# HA_Diagram.net
KiCad netlist of a schematic drawn in Altium Designer
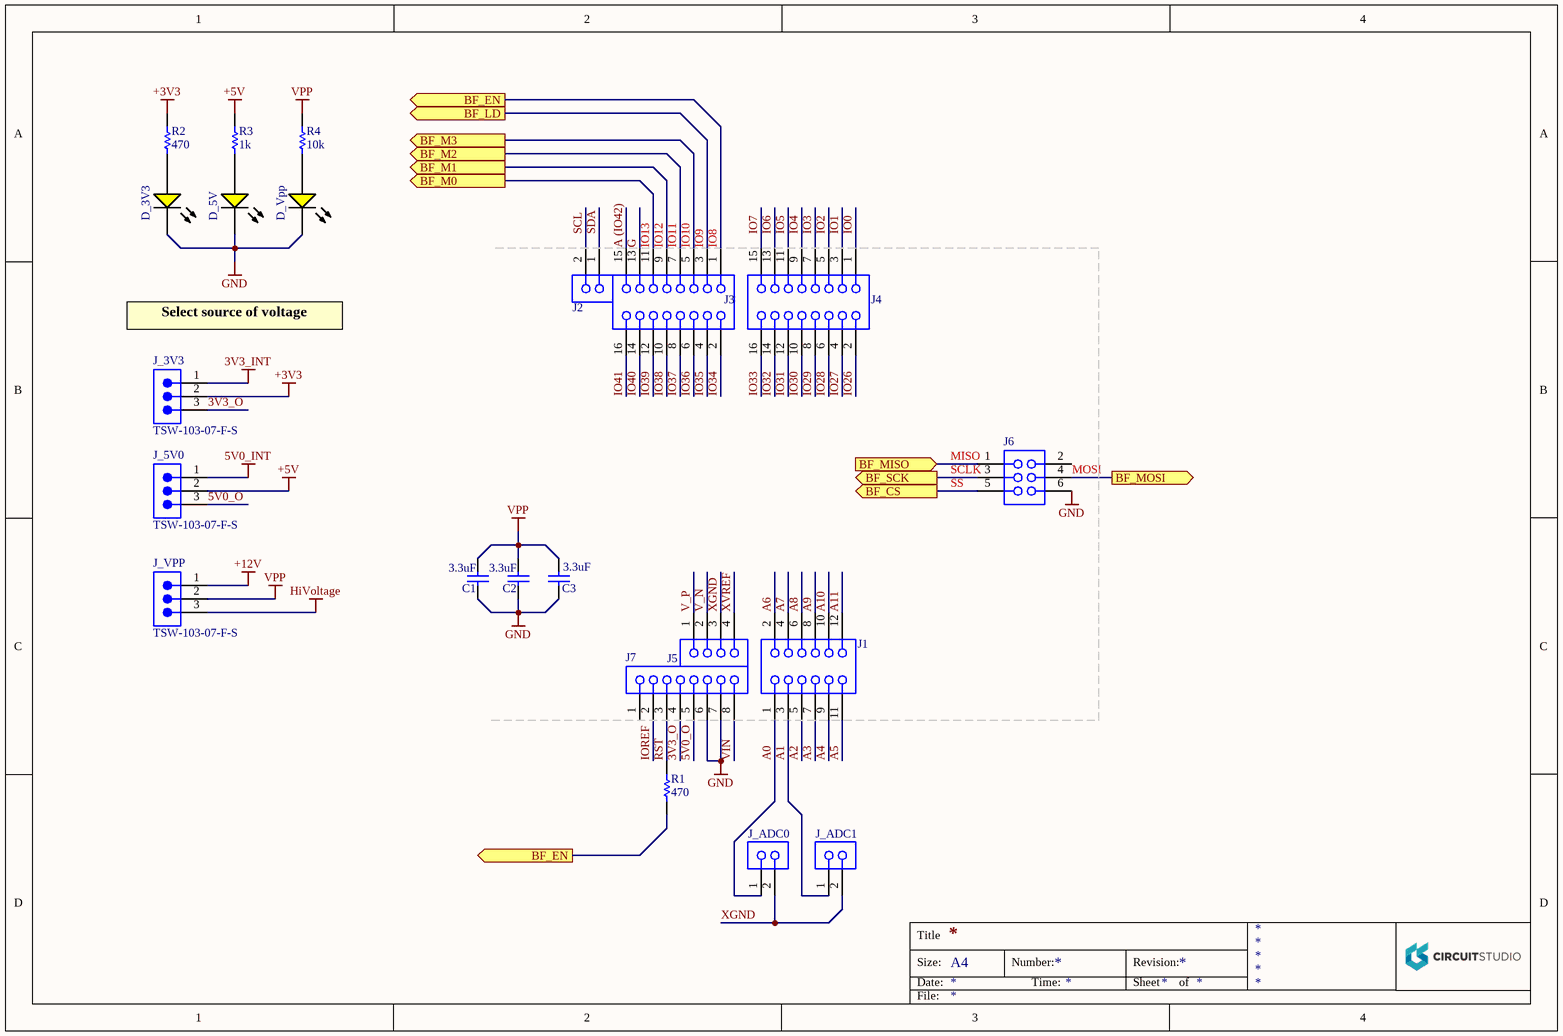
[diagram p0: HA_Diagram.SchDoc]

(export (version "E")
  (design (tool "Eeschema 10.0.6"))
  (components
    (comp (ref "C1")
      (value "3.3uF")
      (footprint "CAPC1206(3216)190_N")
      (description "CAP 3.3uF 100V ±20% 1206 (3216 Metric) Thickness 1.9mm SMD")
      (fields (field (name "TOLERANCE") "Â±20%") (field (name "Comment") "3.3uF 100V"))
      (libsource (lib "Altium Content Vault") (part "CMP-1037-04411-1"))
    )
    (comp (ref "C2")
      (value "3.3uF")
      (footprint "CAPC1206(3216)190_N")
      (description "CAP 3.3uF 100V ±20% 1206 (3216 Metric) Thickness 1.9mm SMD")
      (fields (field (name "TOLERANCE") "Â±20%") (field (name "Comment") "3.3uF 100V"))
      (libsource (lib "Altium Content Vault") (part "CMP-1037-04411-1"))
    )
    (comp (ref "C3")
      (value "3.3uF")
      (footprint "CAPC1206(3216)190_N")
      (description "CAP 3.3uF 100V ±20% 1206 (3216 Metric) Thickness 1.9mm SMD")
      (fields (field (name "TOLERANCE") "Â±20%") (field (name "Comment") "3.3uF 100V"))
      (libsource (lib "Altium Content Vault") (part "CMP-1037-04411-1"))
    )
    (comp (ref "D_3V3")
      (value "LED 0603")
      (footprint "LTST-C190KSKT_V")
      (fields (field (name "TOLERANCE") "1%"))
      (libsource (lib "Altium Content Vault") (part "CMP-1674-00009-1"))
    )
    (comp (ref "D_5V")
      (value "LED 0603")
      (footprint "LTST-C190KSKT_V")
      (fields (field (name "TOLERANCE") "1%"))
      (libsource (lib "Altium Content Vault") (part "CMP-1674-00009-1"))
    )
    (comp (ref "D_Vpp")
      (value "LED 0603")
      (footprint "LTST-C190KSKT_V")
      (fields (field (name "TOLERANCE") "1%"))
      (libsource (lib "Altium Content Vault") (part "CMP-1674-00009-1"))
    )
    (comp (ref "J1")
      (value "SSW-106-01-F-D")
      (footprint "SMTC-SSW-106-01-X-D")
      (description "SQ Post Socket, Through-hole, Vertical, -55 to 125 degC, 2.54mm Pitch, 12-Pin, Female, RoHS")
      (fields (field (name "MANUFACTURER") "Samtec"))
      (libsource (lib "Altium Content Vault") (part "CMP-1023-00357-1"))
    )
    (comp (ref "J2")
      (value "PHF-102-03-L-S")
      (footprint "SMTC-PHF-102-03-X-S")
      (description "Press Fit Socket, Through-hole, Vertical, -55 to 125 degC, 2.54 mm Pitch, 2-Pin, Female, RoHS")
      (fields (field (name "MANUFACTURER") "Samtec"))
      (libsource (lib "") (part "CMP-1023-00105-1_1"))
    )
    (comp (ref "J3")
      (value "ESW-108-12-G-D")
      (footprint "SMTC-ESW-108-12-X-D")
      (description "Elevated Socket, Through-hole, Vertical, -55 to 125 degC, 2.54 mm Pitch, 16-Pin, Female, RoHS")
      (fields (field (name "MANUFACTURER") "Samtec"))
      (libsource (lib "Altium Content Vault") (part "CMP-1023-00046-1"))
    )
    (comp (ref "J4")
      (value "ESW-108-12-G-D")
      (footprint "SMTC-ESW-108-12-X-D")
      (description "Elevated Socket, Through-hole, Vertical, -55 to 125 degC, 2.54 mm Pitch, 16-Pin, Female, RoHS")
      (fields (field (name "MANUFACTURER") "Samtec"))
      (libsource (lib "Altium Content Vault") (part "CMP-1023-00046-1"))
    )
    (comp (ref "J5")
      (value "SLW-104-01-F-S")
      (footprint "SMTC-SLW-104-01-X-S")
      (fields (field (name "MANUFACTURER") "Samtec"))
      (libsource (lib "Altium Content Vault") (part "CMP-1023-00132-1"))
    )
    (comp (ref "J6")
      (value "SSW-103-01-F-D")
      (footprint "SMTC-SSW-103-01-X-D")
      (description "SQ Post Socket, Through-hole, Vertical, -55 to 125 degC, 2.54 mm Pitch, 6-Pin, Female, RoHS")
      (fields (field (name "MANUFACTURER") "Samtec"))
      (libsource (lib "Altium Content Vault") (part "CMP-1023-00329-1"))
    )
    (comp (ref "J7")
      (value "SSQ-108-01-F-S")
      (footprint "SMTC-SSQ-108-01-X-S")
      (description "SQ Post Socket, Through-hole, Vertical, -55 to 125 degC, 2.54 mm Pitch, 8-Pin, Female, RoHS")
      (fields (field (name "MANUFACTURER") "Samtec"))
      (libsource (lib "Altium Content Vault") (part "CMP-1023-00294-1"))
    )
    (comp (ref "J_3V3")
      (value "TSW-103-07-F-S")
      (footprint "SMTC-TSW-103-07-X-S")
      (description "0.025\" SQ Post Header, Through-hole, Vertical, -55 to 125 degC, 2.54 mm Pitch, 3-Pin, Male, RoHS")
      (fields (field (name "MANUFACTURER") "Samtec"))
      (libsource (lib "Altium Content Vault") (part "CMP-1024-00331-1"))
    )
    (comp (ref "J_5V0")
      (value "TSW-103-07-F-S")
      (footprint "SMTC-TSW-103-07-X-S")
      (description "0.025\" SQ Post Header, Through-hole, Vertical, -55 to 125 degC, 2.54 mm Pitch, 3-Pin, Male, RoHS")
      (fields (field (name "MANUFACTURER") "Samtec"))
      (libsource (lib "Altium Content Vault") (part "CMP-1024-00331-1"))
    )
    (comp (ref "J_ADC0")
      (value "PHF-102-03-L-S")
      (footprint "SMTC-PHF-102-03-X-S")
      (description "Press Fit Socket, Through-hole, Vertical, -55 to 125 degC, 2.54 mm Pitch, 2-Pin, Female, RoHS")
      (fields (field (name "MANUFACTURER") "Samtec"))
      (libsource (lib "Altium Content Vault") (part "CMP-1023-00105-1"))
    )
    (comp (ref "J_ADC1")
      (value "PHF-102-03-L-S")
      (footprint "SMTC-PHF-102-03-X-S")
      (description "Press Fit Socket, Through-hole, Vertical, -55 to 125 degC, 2.54 mm Pitch, 2-Pin, Female, RoHS")
      (fields (field (name "MANUFACTURER") "Samtec"))
      (libsource (lib "Altium Content Vault") (part "CMP-1023-00105-1"))
    )
    (comp (ref "J_VPP")
      (value "TSW-103-07-F-S")
      (footprint "SMTC-TSW-103-07-X-S")
      (description "0.025\" SQ Post Header, Through-hole, Vertical, -55 to 125 degC, 2.54 mm Pitch, 3-Pin, Male, RoHS")
      (fields (field (name "MANUFACTURER") "Samtec"))
      (libsource (lib "Altium Content Vault") (part "CMP-1024-00331-1"))
    )
    (comp (ref "R1")
      (value "470")
      (footprint "RESC0603(1608)_N")
      (description "200 1% 0603 SMD")
      (fields (field (name "TOLERANCE") "1 %"))
      (libsource (lib "Altium Content Vault") (part "CMP-1012-00122-1"))
    )
    (comp (ref "R2")
      (value "470")
      (footprint "RESC0603(1608)_N")
      (description "200 1% 0603 SMD")
      (fields (field (name "TOLERANCE") "1 %"))
      (libsource (lib "Altium Content Vault") (part "CMP-1012-00122-1"))
    )
    (comp (ref "R3")
      (value "1k")
      (footprint "RESC0603(1608)_N")
      (description "200 1% 0603 SMD")
      (fields (field (name "TOLERANCE") "1 %"))
      (libsource (lib "Altium Content Vault") (part "CMP-1012-00122-1"))
    )
    (comp (ref "R4")
      (value "10k")
      (footprint "RESC0603(1608)_N")
      (description "200 1% 0603 SMD")
      (fields (field (name "TOLERANCE") "1 %"))
      (libsource (lib "Altium Content Vault") (part "CMP-1012-00122-1"))
    )
  )
  (nets
    (net (code "1") (name "+3V3") (class "Default")
      (node (ref "J_3V3") (pin "2") (pinfunction "2_2") (pintype "passive"))
      (node (ref "R2") (pin "1") (pinfunction "1_1") (pintype "passive"))
    )
    (net (code "2") (name "+5V") (class "Default")
      (node (ref "J_5V0") (pin "2") (pinfunction "2_2") (pintype "passive"))
      (node (ref "R3") (pin "1") (pinfunction "1_1") (pintype "passive"))
    )
    (net (code "3") (name "+12V") (class "Default")
      (node (ref "J_VPP") (pin "1") (pinfunction "1_1") (pintype "passive"))
    )
    (net (code "4") (name "/3V3_O") (class "Default")
      (node (ref "J7") (pin "4") (pinfunction "4_4") (pintype "passive"))
      (node (ref "J_3V3") (pin "3") (pinfunction "3_3") (pintype "passive"))
    )
    (net (code "5") (name "/5V0_O") (class "Default")
      (node (ref "J7") (pin "5") (pinfunction "5_5") (pintype "passive"))
      (node (ref "J_5V0") (pin "3") (pinfunction "3_3") (pintype "passive"))
    )
    (net (code "6") (name "/A (IO42)") (class "Default")
      (node (ref "J3") (pin "15") (pinfunction "15_15") (pintype "passive"))
    )
    (net (code "7") (name "/A0") (class "Default")
      (node (ref "J1") (pin "1") (pinfunction "1_1") (pintype "passive"))
      (node (ref "J_ADC0") (pin "1") (pinfunction "1_1") (pintype "passive"))
    )
    (net (code "8") (name "/A1") (class "Default")
      (node (ref "J1") (pin "3") (pinfunction "3_3") (pintype "passive"))
      (node (ref "J_ADC1") (pin "1") (pinfunction "1_1") (pintype "passive"))
    )
    (net (code "9") (name "/A2") (class "Default")
      (node (ref "J1") (pin "5") (pinfunction "5_5") (pintype "passive"))
    )
    (net (code "10") (name "/A3") (class "Default")
      (node (ref "J1") (pin "7") (pinfunction "7_7") (pintype "passive"))
    )
    (net (code "11") (name "/A4") (class "Default")
      (node (ref "J1") (pin "9") (pinfunction "9_9") (pintype "passive"))
    )
    (net (code "12") (name "/A5") (class "Default")
      (node (ref "J1") (pin "11") (pinfunction "11_11") (pintype "passive"))
    )
    (net (code "13") (name "/A6") (class "Default")
      (node (ref "J1") (pin "2") (pinfunction "2_2") (pintype "passive"))
    )
    (net (code "14") (name "/A7") (class "Default")
      (node (ref "J1") (pin "4") (pinfunction "4_4") (pintype "passive"))
    )
    (net (code "15") (name "/A8") (class "Default")
      (node (ref "J1") (pin "6") (pinfunction "6_6") (pintype "passive"))
    )
    (net (code "16") (name "/A9") (class "Default")
      (node (ref "J1") (pin "8") (pinfunction "8_8") (pintype "passive"))
    )
    (net (code "17") (name "/A10") (class "Default")
      (node (ref "J1") (pin "10") (pinfunction "10_10") (pintype "passive"))
    )
    (net (code "18") (name "/A11") (class "Default")
      (node (ref "J1") (pin "12") (pinfunction "12_12") (pintype "passive"))
    )
    (net (code "19") (name "/BF_CS") (class "Default")
      (node (ref "J6") (pin "5") (pinfunction "5_5") (pintype "passive"))
    )
    (net (code "20") (name "/BF_EN") (class "Default")
      (node (ref "J3") (pin "1") (pinfunction "1_1") (pintype "passive"))
      (node (ref "R1") (pin "2") (pinfunction "2_2") (pintype "passive"))
    )
    (net (code "21") (name "/BF_LD") (class "Default")
      (node (ref "J3") (pin "3") (pinfunction "3_3") (pintype "passive"))
    )
    (net (code "22") (name "/BF_M0") (class "Default")
      (node (ref "J3") (pin "11") (pinfunction "11_11") (pintype "passive"))
    )
    (net (code "23") (name "/BF_M1") (class "Default")
      (node (ref "J3") (pin "9") (pinfunction "9_9") (pintype "passive"))
    )
    (net (code "24") (name "/BF_M2") (class "Default")
      (node (ref "J3") (pin "7") (pinfunction "7_7") (pintype "passive"))
    )
    (net (code "25") (name "/BF_M3") (class "Default")
      (node (ref "J3") (pin "5") (pinfunction "5_5") (pintype "passive"))
    )
    (net (code "26") (name "/BF_MISO") (class "Default")
      (node (ref "J6") (pin "1") (pinfunction "1_1") (pintype "passive"))
    )
    (net (code "27") (name "/BF_MOSI") (class "Default")
      (node (ref "J6") (pin "4") (pinfunction "4_4") (pintype "passive"))
    )
    (net (code "28") (name "/BF_SCK") (class "Default")
      (node (ref "J6") (pin "3") (pinfunction "3_3") (pintype "passive"))
    )
    (net (code "29") (name "/G") (class "Default")
      (node (ref "J3") (pin "13") (pinfunction "13_13") (pintype "passive"))
    )
    (net (code "30") (name "/IO0") (class "Default")
      (node (ref "J4") (pin "1") (pinfunction "1_1") (pintype "passive"))
    )
    (net (code "31") (name "/IO1") (class "Default")
      (node (ref "J4") (pin "3") (pinfunction "3_3") (pintype "passive"))
    )
    (net (code "32") (name "/IO2") (class "Default")
      (node (ref "J4") (pin "5") (pinfunction "5_5") (pintype "passive"))
    )
    (net (code "33") (name "/IO3") (class "Default")
      (node (ref "J4") (pin "7") (pinfunction "7_7") (pintype "passive"))
    )
    (net (code "34") (name "/IO4") (class "Default")
      (node (ref "J4") (pin "9") (pinfunction "9_9") (pintype "passive"))
    )
    (net (code "35") (name "/IO5") (class "Default")
      (node (ref "J4") (pin "11") (pinfunction "11_11") (pintype "passive"))
    )
    (net (code "36") (name "/IO6") (class "Default")
      (node (ref "J4") (pin "13") (pinfunction "13_13") (pintype "passive"))
    )
    (net (code "37") (name "/IO7") (class "Default")
      (node (ref "J4") (pin "15") (pinfunction "15_15") (pintype "passive"))
    )
    (net (code "38") (name "/IO26") (class "Default")
      (node (ref "J4") (pin "2") (pinfunction "2_2") (pintype "passive"))
    )
    (net (code "39") (name "/IO27") (class "Default")
      (node (ref "J4") (pin "4") (pinfunction "4_4") (pintype "passive"))
    )
    (net (code "40") (name "/IO28") (class "Default")
      (node (ref "J4") (pin "6") (pinfunction "6_6") (pintype "passive"))
    )
    (net (code "41") (name "/IO29") (class "Default")
      (node (ref "J4") (pin "8") (pinfunction "8_8") (pintype "passive"))
    )
    (net (code "42") (name "/IO30") (class "Default")
      (node (ref "J4") (pin "10") (pinfunction "10_10") (pintype "passive"))
    )
    (net (code "43") (name "/IO31") (class "Default")
      (node (ref "J4") (pin "12") (pinfunction "12_12") (pintype "passive"))
    )
    (net (code "44") (name "/IO32") (class "Default")
      (node (ref "J4") (pin "14") (pinfunction "14_14") (pintype "passive"))
    )
    (net (code "45") (name "/IO33") (class "Default")
      (node (ref "J4") (pin "16") (pinfunction "16_16") (pintype "passive"))
    )
    (net (code "46") (name "/IO34") (class "Default")
      (node (ref "J3") (pin "2") (pinfunction "2_2") (pintype "passive"))
    )
    (net (code "47") (name "/IO35") (class "Default")
      (node (ref "J3") (pin "4") (pinfunction "4_4") (pintype "passive"))
    )
    (net (code "48") (name "/IO36") (class "Default")
      (node (ref "J3") (pin "6") (pinfunction "6_6") (pintype "passive"))
    )
    (net (code "49") (name "/IO37") (class "Default")
      (node (ref "J3") (pin "8") (pinfunction "8_8") (pintype "passive"))
    )
    (net (code "50") (name "/IO38") (class "Default")
      (node (ref "J3") (pin "10") (pinfunction "10_10") (pintype "passive"))
    )
    (net (code "51") (name "/IO39") (class "Default")
      (node (ref "J3") (pin "12") (pinfunction "12_12") (pintype "passive"))
    )
    (net (code "52") (name "/IO40") (class "Default")
      (node (ref "J3") (pin "14") (pinfunction "14_14") (pintype "passive"))
    )
    (net (code "53") (name "/IO41") (class "Default")
      (node (ref "J3") (pin "16") (pinfunction "16_16") (pintype "passive"))
    )
    (net (code "54") (name "/IOREF") (class "Default")
      (node (ref "J7") (pin "2") (pinfunction "2_2") (pintype "passive"))
    )
    (net (code "55") (name "/RST") (class "Default")
      (node (ref "J7") (pin "3") (pinfunction "3_3") (pintype "passive"))
      (node (ref "R1") (pin "1") (pinfunction "1_1") (pintype "passive"))
    )
    (net (code "56") (name "/SCL") (class "Default")
      (node (ref "J2") (pin "2") (pinfunction "2_2") (pintype "passive"))
    )
    (net (code "57") (name "/SDA") (class "Default")
      (node (ref "J2") (pin "1") (pinfunction "1_1") (pintype "passive"))
    )
    (net (code "58") (name "/VIN") (class "Default")
      (node (ref "J7") (pin "8") (pinfunction "8_8") (pintype "passive"))
    )
    (net (code "59") (name "/V_N") (class "Default")
      (node (ref "J5") (pin "2") (pinfunction "2_2") (pintype "passive"))
    )
    (net (code "60") (name "/V_P") (class "Default")
      (node (ref "J5") (pin "1") (pinfunction "1_1") (pintype "passive"))
    )
    (net (code "61") (name "/XGND") (class "Default")
      (node (ref "J5") (pin "3") (pinfunction "3_3") (pintype "passive"))
      (node (ref "J_ADC0") (pin "2") (pinfunction "2_2") (pintype "passive"))
      (node (ref "J_ADC1") (pin "2") (pinfunction "2_2") (pintype "passive"))
    )
    (net (code "62") (name "/XVREF") (class "Default")
      (node (ref "J5") (pin "4") (pinfunction "4_4") (pintype "passive"))
    )
    (net (code "63") (name "3V3_INT") (class "Default")
      (node (ref "J_3V3") (pin "1") (pinfunction "1_1") (pintype "passive"))
    )
    (net (code "64") (name "5V0_INT") (class "Default")
      (node (ref "J_5V0") (pin "1") (pinfunction "1_1") (pintype "passive"))
    )
    (net (code "65") (name "GND") (class "Default")
      (node (ref "C1") (pin "1") (pinfunction "1_1") (pintype "passive"))
      (node (ref "C2") (pin "1") (pinfunction "1_1") (pintype "passive"))
      (node (ref "C3") (pin "1") (pinfunction "1_1") (pintype "passive"))
      (node (ref "D_3V3") (pin "2") (pinfunction "K_2") (pintype "passive"))
      (node (ref "D_5V") (pin "2") (pinfunction "K_2") (pintype "passive"))
      (node (ref "D_Vpp") (pin "2") (pinfunction "K_2") (pintype "passive"))
      (node (ref "J6") (pin "6") (pinfunction "6_6") (pintype "passive"))
      (node (ref "J7") (pin "6") (pinfunction "6_6") (pintype "passive"))
      (node (ref "J7") (pin "7") (pinfunction "7_7") (pintype "passive"))
    )
    (net (code "66") (name "HiVoltage") (class "Default")
      (node (ref "J_VPP") (pin "3") (pinfunction "3_3") (pintype "passive"))
    )
    (net (code "67") (name "Net-(D_3V3-A)") (class "Default")
      (node (ref "D_3V3") (pin "1") (pinfunction "A_1") (pintype "passive"))
      (node (ref "R2") (pin "2") (pinfunction "2_2") (pintype "passive"))
    )
    (net (code "68") (name "Net-(D_5V-A)") (class "Default")
      (node (ref "D_5V") (pin "1") (pinfunction "A_1") (pintype "passive"))
      (node (ref "R3") (pin "2") (pinfunction "2_2") (pintype "passive"))
    )
    (net (code "69") (name "Net-(D_Vpp-A)") (class "Default")
      (node (ref "D_Vpp") (pin "1") (pinfunction "A_1") (pintype "passive"))
      (node (ref "R4") (pin "2") (pinfunction "2_2") (pintype "passive"))
    )
    (net (code "70") (name "VPP") (class "Default")
      (node (ref "C1") (pin "2") (pinfunction "2_2") (pintype "passive"))
      (node (ref "C2") (pin "2") (pinfunction "2_2") (pintype "passive"))
      (node (ref "C3") (pin "2") (pinfunction "2_2") (pintype "passive"))
      (node (ref "J_VPP") (pin "2") (pinfunction "2_2") (pintype "passive"))
      (node (ref "R4") (pin "1") (pinfunction "1_1") (pintype "passive"))
    )
    (net (code "71") (name "unconnected-(J6-Pad2)") (class "Default")
      (node (ref "J6") (pin "2") (pinfunction "2_2") (pintype "passive"))
    )
    (net (code "72") (name "unconnected-(J7-Pad1)") (class "Default")
      (node (ref "J7") (pin "1") (pinfunction "1_1") (pintype "passive"))
    )
  )
)
